# panel.net
KiCad netlist of a schematic drawn in Altium Designer
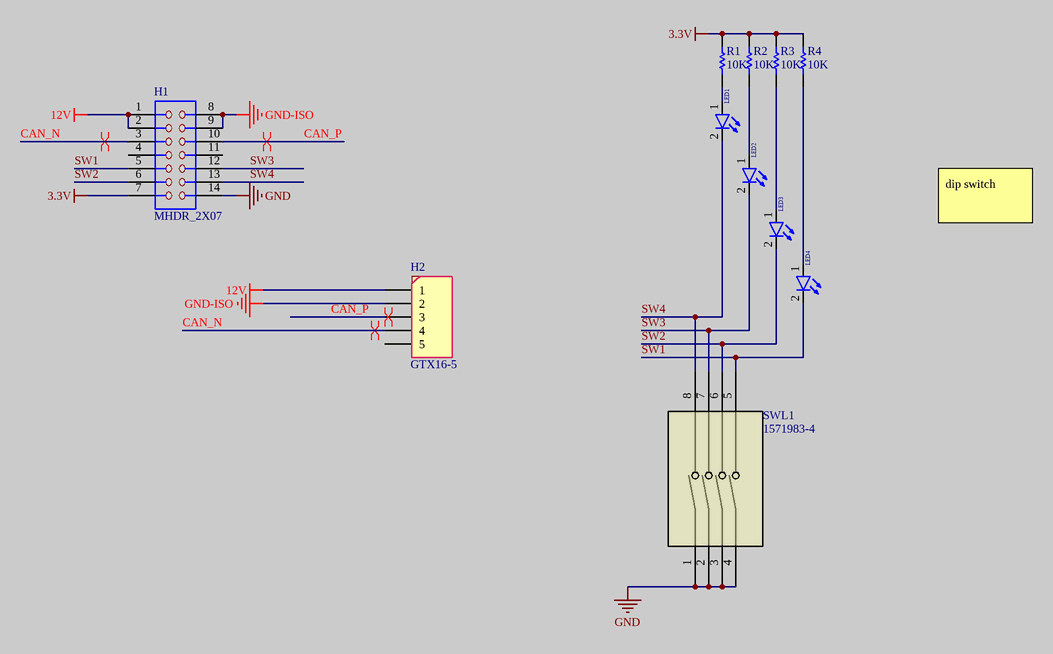
[diagram p0: panel.SchDoc]

(export (version "E")
  (design (tool "Eeschema 10.0.6"))
  (components
    (comp (ref "H1")
      (value "MHDR_2X07")
      (footprint "miniATX 2 × 7")
      (description "Male Header 2X07")
      (libsource (lib "eLIB") (part "HDR_mini_2 × 7"))
    )
    (comp (ref "H2")
      (value "GTX16-5")
      (footprint "GX16-5PIN")
      (fields (field (name "PUBLISHER") "Altium Limited"))
      (libsource (lib "SINA") (part "Header1*5"))
    )
    (comp (ref "LED1")
      (value "Red")
      (footprint "LED 3mm")
      (description "LED")
      (fields (field (name "DESIGNER") "Saeid Jorablo"))
      (libsource (lib "TaraSchlib") (part "LED"))
    )
    (comp (ref "LED2")
      (value "Red")
      (footprint "LED 3mm")
      (description "LED")
      (fields (field (name "DESIGNER") "Saeid Jorablo"))
      (libsource (lib "TaraSchlib") (part "LED"))
    )
    (comp (ref "LED3")
      (value "Red")
      (footprint "LED 3mm")
      (description "LED")
      (fields (field (name "DESIGNER") "Saeid Jorablo"))
      (libsource (lib "TaraSchlib") (part "LED"))
    )
    (comp (ref "LED4")
      (value "Red")
      (footprint "LED 3mm")
      (description "LED")
      (fields (field (name "DESIGNER") "Saeid Jorablo"))
      (libsource (lib "TaraSchlib") (part "LED"))
    )
    (comp (ref "R1")
      (value "10K")
      (footprint "RES0603")
      (description "0603,0.1W")
      (fields (field (name "PUBLISHER") "Altium Limited"))
      (libsource (lib "eLIB") (part "Resistor"))
    )
    (comp (ref "R2")
      (value "10K")
      (footprint "RES0603")
      (description "0603,0.1W")
      (fields (field (name "PUBLISHER") "Altium Limited"))
      (libsource (lib "eLIB") (part "Resistor"))
    )
    (comp (ref "R3")
      (value "10K")
      (footprint "RES0603")
      (description "0603,0.1W")
      (fields (field (name "PUBLISHER") "Altium Limited"))
      (libsource (lib "eLIB") (part "Resistor"))
    )
    (comp (ref "R4")
      (value "10K")
      (footprint "RES0603")
      (description "0603,0.1W")
      (fields (field (name "PUBLISHER") "Altium Limited"))
      (libsource (lib "eLIB") (part "Resistor"))
    )
    (comp (ref "SWL1")
      (value "1571983-4")
      (footprint "SW4_1571983_4P_TEC")
      (description "GDH04S04=DIP SWITCH")
      (fields (field (name "COPYRIGHT") "Copyright (C) 2025 Ultra Librarian. All rights reserved."))
      (libsource (lib "SINA") (part "1571983-4"))
    )
  )
  (nets
    (net (code "1") (name "/CAN_N") (class "Default")
      (node (ref "H1") (pin "3") (pinfunction "3_3") (pintype "passive"))
      (node (ref "H2") (pin "4") (pinfunction "4_4") (pintype "passive"))
    )
    (net (code "2") (name "/CAN_P") (class "Default")
      (node (ref "H1") (pin "10") (pinfunction "10_10") (pintype "passive"))
      (node (ref "H2") (pin "3") (pinfunction "3_3") (pintype "passive"))
    )
    (net (code "3") (name "/SW1") (class "Default")
      (node (ref "H1") (pin "5") (pinfunction "5_5") (pintype "passive"))
      (node (ref "LED4") (pin "2") (pinfunction "K_2") (pintype "passive"))
      (node (ref "SWL1") (pin "5") (pinfunction "5_5") (pintype "passive"))
    )
    (net (code "4") (name "/SW2") (class "Default")
      (node (ref "H1") (pin "6") (pinfunction "6_6") (pintype "passive"))
      (node (ref "LED3") (pin "2") (pinfunction "K_2") (pintype "passive"))
      (node (ref "SWL1") (pin "6") (pinfunction "6_6") (pintype "passive"))
    )
    (net (code "5") (name "/SW3") (class "Default")
      (node (ref "H1") (pin "12") (pinfunction "12_12") (pintype "passive"))
      (node (ref "LED2") (pin "2") (pinfunction "K_2") (pintype "passive"))
      (node (ref "SWL1") (pin "7") (pinfunction "7_7") (pintype "passive"))
    )
    (net (code "6") (name "/SW4") (class "Default")
      (node (ref "H1") (pin "13") (pinfunction "13_13") (pintype "passive"))
      (node (ref "LED1") (pin "2") (pinfunction "K_2") (pintype "passive"))
      (node (ref "SWL1") (pin "8") (pinfunction "8_8") (pintype "passive"))
    )
    (net (code "7") (name "3.3V") (class "Default")
      (node (ref "H1") (pin "7") (pinfunction "7_7") (pintype "passive"))
      (node (ref "R1") (pin "2") (pinfunction "2_2") (pintype "passive"))
      (node (ref "R2") (pin "2") (pinfunction "2_2") (pintype "passive"))
      (node (ref "R3") (pin "2") (pinfunction "2_2") (pintype "passive"))
      (node (ref "R4") (pin "2") (pinfunction "2_2") (pintype "passive"))
    )
    (net (code "8") (name "12V") (class "Default")
      (node (ref "H1") (pin "1") (pinfunction "1_1") (pintype "passive"))
      (node (ref "H1") (pin "2") (pinfunction "2_2") (pintype "passive"))
      (node (ref "H2") (pin "1") (pinfunction "1_1") (pintype "passive"))
    )
    (net (code "9") (name "GND") (class "Default")
      (node (ref "H1") (pin "14") (pinfunction "14_14") (pintype "passive"))
      (node (ref "SWL1") (pin "1") (pinfunction "1_1") (pintype "passive"))
      (node (ref "SWL1") (pin "2") (pinfunction "2_2") (pintype "passive"))
      (node (ref "SWL1") (pin "3") (pinfunction "3_3") (pintype "passive"))
      (node (ref "SWL1") (pin "4") (pinfunction "4_4") (pintype "passive"))
    )
    (net (code "10") (name "GND-ISO") (class "Default")
      (node (ref "H1") (pin "8") (pinfunction "8_8") (pintype "passive"))
      (node (ref "H1") (pin "9") (pinfunction "9_9") (pintype "passive"))
      (node (ref "H2") (pin "2") (pinfunction "2_2") (pintype "passive"))
    )
    (net (code "11") (name "Net-(LED1-A)") (class "Default")
      (node (ref "LED1") (pin "1") (pinfunction "A_1") (pintype "passive"))
      (node (ref "R1") (pin "1") (pinfunction "1_1") (pintype "passive"))
    )
    (net (code "12") (name "Net-(LED2-A)") (class "Default")
      (node (ref "LED2") (pin "1") (pinfunction "A_1") (pintype "passive"))
      (node (ref "R2") (pin "1") (pinfunction "1_1") (pintype "passive"))
    )
    (net (code "13") (name "Net-(LED3-A)") (class "Default")
      (node (ref "LED3") (pin "1") (pinfunction "A_1") (pintype "passive"))
      (node (ref "R3") (pin "1") (pinfunction "1_1") (pintype "passive"))
    )
    (net (code "14") (name "Net-(LED4-A)") (class "Default")
      (node (ref "LED4") (pin "1") (pinfunction "A_1") (pintype "passive"))
      (node (ref "R4") (pin "1") (pinfunction "1_1") (pintype "passive"))
    )
    (net (code "15") (name "unconnected-(H1-Pad4)") (class "Default")
      (node (ref "H1") (pin "4") (pinfunction "4_4") (pintype "passive"))
    )
    (net (code "16") (name "unconnected-(H1-Pad11)") (class "Default")
      (node (ref "H1") (pin "11") (pinfunction "11_11") (pintype "passive"))
    )
    (net (code "17") (name "unconnected-(H2-Pad5)") (class "Default")
      (node (ref "H2") (pin "5") (pinfunction "5_5") (pintype "passive"))
    )
  )
)
